# MOSFET_Sheet.net
KiCad netlist of a schematic drawn in Altium Designer
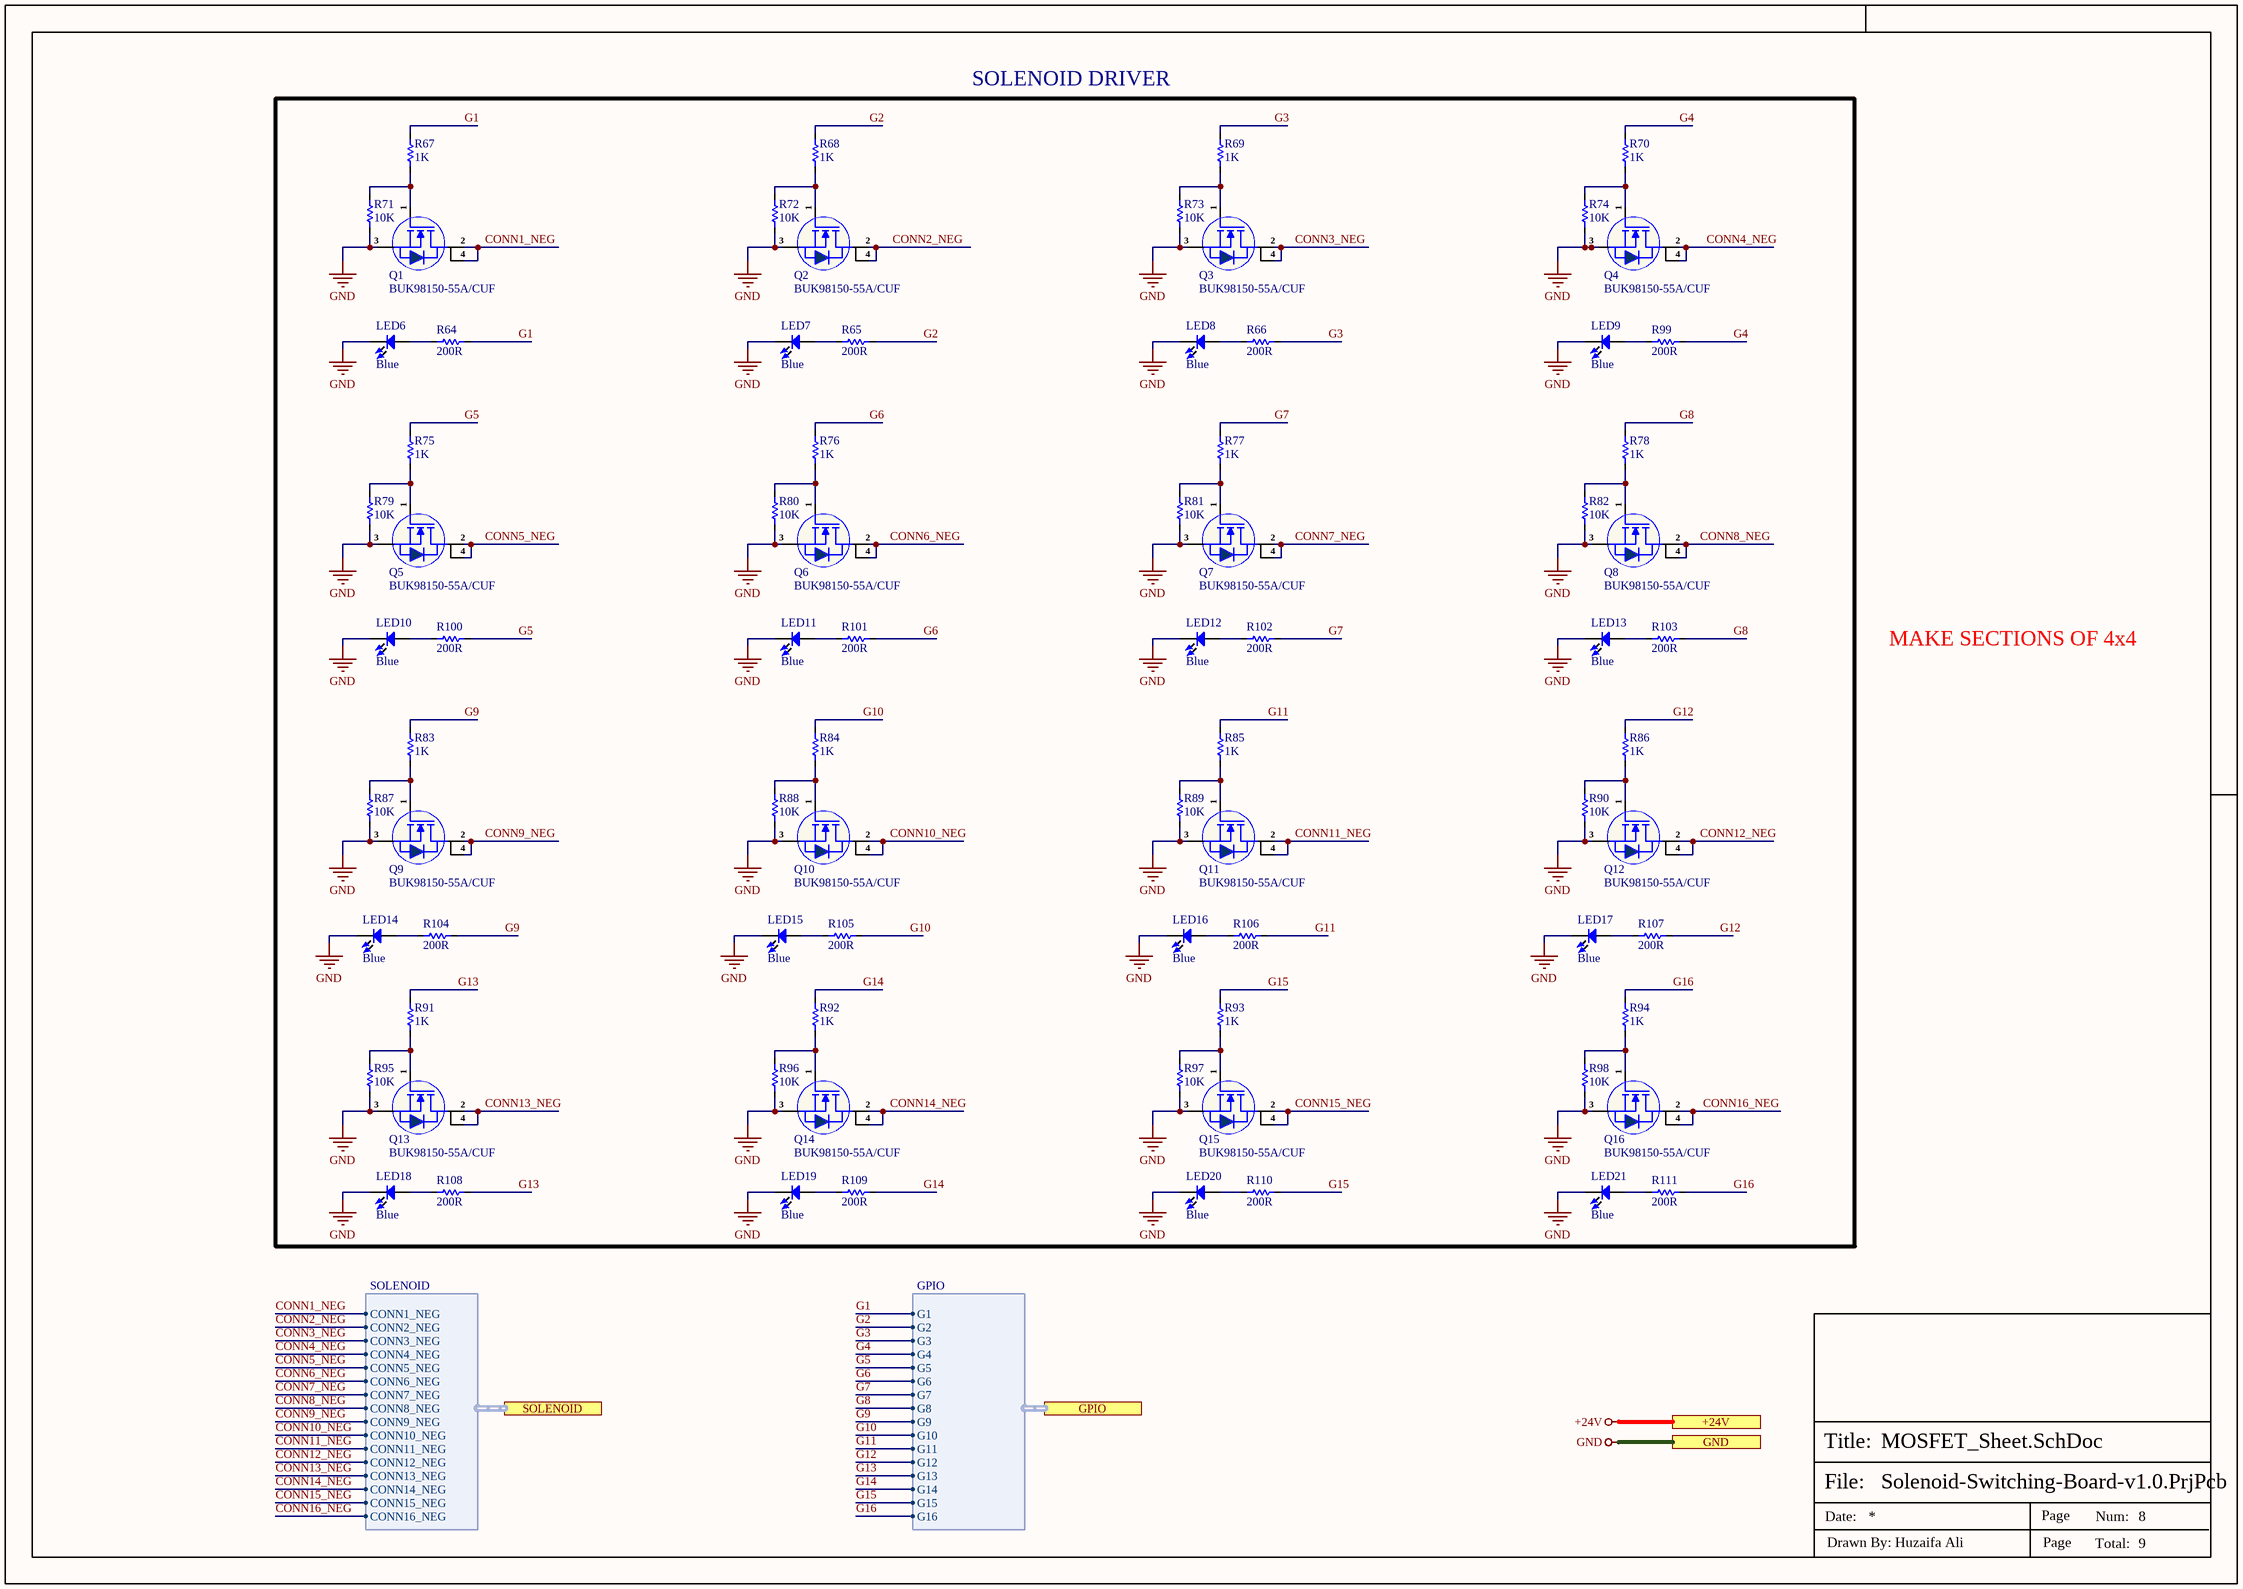
[diagram p0: MOSFET_Sheet.SchDoc]

(export (version "E")
  (design (tool "Eeschema 10.0.6"))
  (components
    (comp (ref "LED6")
      (value "Blue")
      (footprint "LED-0603")
      (description "blue 0603 Light Emitting Diodes (LED) ROHS")
      (fields
        (field (name "MANUFACTURER") "Foshan NationStar Optoelectronics")
        (field (name "MANUFACTURER PART NUMBER") "NCD0603B3")
      )
      (libsource (lib "eSpark Libraries") (part "NCD0603B3"))
    )
    (comp (ref "LED7")
      (value "Blue")
      (footprint "LED-0603")
      (description "blue 0603 Light Emitting Diodes (LED) ROHS")
      (fields
        (field (name "MANUFACTURER") "Foshan NationStar Optoelectronics")
        (field (name "MANUFACTURER PART NUMBER") "NCD0603B3")
      )
      (libsource (lib "eSpark Libraries") (part "NCD0603B3"))
    )
    (comp (ref "LED8")
      (value "Blue")
      (footprint "LED-0603")
      (description "blue 0603 Light Emitting Diodes (LED) ROHS")
      (fields
        (field (name "MANUFACTURER") "Foshan NationStar Optoelectronics")
        (field (name "MANUFACTURER PART NUMBER") "NCD0603B3")
      )
      (libsource (lib "eSpark Libraries") (part "NCD0603B3"))
    )
    (comp (ref "LED9")
      (value "Blue")
      (footprint "LED-0603")
      (description "blue 0603 Light Emitting Diodes (LED) ROHS")
      (fields
        (field (name "MANUFACTURER") "Foshan NationStar Optoelectronics")
        (field (name "MANUFACTURER PART NUMBER") "NCD0603B3")
      )
      (libsource (lib "eSpark Libraries") (part "NCD0603B3"))
    )
    (comp (ref "LED10")
      (value "Blue")
      (footprint "LED-0603")
      (description "blue 0603 Light Emitting Diodes (LED) ROHS")
      (fields
        (field (name "MANUFACTURER") "Foshan NationStar Optoelectronics")
        (field (name "MANUFACTURER PART NUMBER") "NCD0603B3")
      )
      (libsource (lib "eSpark Libraries") (part "NCD0603B3"))
    )
    (comp (ref "LED11")
      (value "Blue")
      (footprint "LED-0603")
      (description "blue 0603 Light Emitting Diodes (LED) ROHS")
      (fields
        (field (name "MANUFACTURER") "Foshan NationStar Optoelectronics")
        (field (name "MANUFACTURER PART NUMBER") "NCD0603B3")
      )
      (libsource (lib "eSpark Libraries") (part "NCD0603B3"))
    )
    (comp (ref "LED12")
      (value "Blue")
      (footprint "LED-0603")
      (description "blue 0603 Light Emitting Diodes (LED) ROHS")
      (fields
        (field (name "MANUFACTURER") "Foshan NationStar Optoelectronics")
        (field (name "MANUFACTURER PART NUMBER") "NCD0603B3")
      )
      (libsource (lib "eSpark Libraries") (part "NCD0603B3"))
    )
    (comp (ref "LED13")
      (value "Blue")
      (footprint "LED-0603")
      (description "blue 0603 Light Emitting Diodes (LED) ROHS")
      (fields
        (field (name "MANUFACTURER") "Foshan NationStar Optoelectronics")
        (field (name "MANUFACTURER PART NUMBER") "NCD0603B3")
      )
      (libsource (lib "eSpark Libraries") (part "NCD0603B3"))
    )
    (comp (ref "LED14")
      (value "Blue")
      (footprint "LED-0603")
      (description "blue 0603 Light Emitting Diodes (LED) ROHS")
      (fields
        (field (name "MANUFACTURER") "Foshan NationStar Optoelectronics")
        (field (name "MANUFACTURER PART NUMBER") "NCD0603B3")
      )
      (libsource (lib "eSpark Libraries") (part "NCD0603B3"))
    )
    (comp (ref "LED15")
      (value "Blue")
      (footprint "LED-0603")
      (description "blue 0603 Light Emitting Diodes (LED) ROHS")
      (fields
        (field (name "MANUFACTURER") "Foshan NationStar Optoelectronics")
        (field (name "MANUFACTURER PART NUMBER") "NCD0603B3")
      )
      (libsource (lib "eSpark Libraries") (part "NCD0603B3"))
    )
    (comp (ref "LED16")
      (value "Blue")
      (footprint "LED-0603")
      (description "blue 0603 Light Emitting Diodes (LED) ROHS")
      (fields
        (field (name "MANUFACTURER") "Foshan NationStar Optoelectronics")
        (field (name "MANUFACTURER PART NUMBER") "NCD0603B3")
      )
      (libsource (lib "eSpark Libraries") (part "NCD0603B3"))
    )
    (comp (ref "LED17")
      (value "Blue")
      (footprint "LED-0603")
      (description "blue 0603 Light Emitting Diodes (LED) ROHS")
      (fields
        (field (name "MANUFACTURER") "Foshan NationStar Optoelectronics")
        (field (name "MANUFACTURER PART NUMBER") "NCD0603B3")
      )
      (libsource (lib "eSpark Libraries") (part "NCD0603B3"))
    )
    (comp (ref "LED18")
      (value "Blue")
      (footprint "LED-0603")
      (description "blue 0603 Light Emitting Diodes (LED) ROHS")
      (fields
        (field (name "MANUFACTURER") "Foshan NationStar Optoelectronics")
        (field (name "MANUFACTURER PART NUMBER") "NCD0603B3")
      )
      (libsource (lib "eSpark Libraries") (part "NCD0603B3"))
    )
    (comp (ref "LED19")
      (value "Blue")
      (footprint "LED-0603")
      (description "blue 0603 Light Emitting Diodes (LED) ROHS")
      (fields
        (field (name "MANUFACTURER") "Foshan NationStar Optoelectronics")
        (field (name "MANUFACTURER PART NUMBER") "NCD0603B3")
      )
      (libsource (lib "eSpark Libraries") (part "NCD0603B3"))
    )
    (comp (ref "LED20")
      (value "Blue")
      (footprint "LED-0603")
      (description "blue 0603 Light Emitting Diodes (LED) ROHS")
      (fields
        (field (name "MANUFACTURER") "Foshan NationStar Optoelectronics")
        (field (name "MANUFACTURER PART NUMBER") "NCD0603B3")
      )
      (libsource (lib "eSpark Libraries") (part "NCD0603B3"))
    )
    (comp (ref "LED21")
      (value "Blue")
      (footprint "LED-0603")
      (description "blue 0603 Light Emitting Diodes (LED) ROHS")
      (fields
        (field (name "MANUFACTURER") "Foshan NationStar Optoelectronics")
        (field (name "MANUFACTURER PART NUMBER") "NCD0603B3")
      )
      (libsource (lib "eSpark Libraries") (part "NCD0603B3"))
    )
    (comp (ref "Q1")
      (value "BUK98150-55A/CUF")
      (footprint "SOT- 223")
      (description "MOSFET N-CH 55V 5.5A SOT223")
      (fields (field (name "LCSC PART NUMBER") "C458219") (field (name "MANUFACTURER") "Nexperia"))
      (libsource (lib "eSpark Libraries") (part "BUK98150-55A/CUF"))
    )
    (comp (ref "Q2")
      (value "BUK98150-55A/CUF")
      (footprint "SOT- 223")
      (description "MOSFET N-CH 55V 5.5A SOT223")
      (fields (field (name "LCSC PART NUMBER") "C458219") (field (name "MANUFACTURER") "Nexperia"))
      (libsource (lib "eSpark Libraries") (part "BUK98150-55A/CUF"))
    )
    (comp (ref "Q3")
      (value "BUK98150-55A/CUF")
      (footprint "SOT- 223")
      (description "MOSFET N-CH 55V 5.5A SOT223")
      (fields (field (name "LCSC PART NUMBER") "C458219") (field (name "MANUFACTURER") "Nexperia"))
      (libsource (lib "eSpark Libraries") (part "BUK98150-55A/CUF"))
    )
    (comp (ref "Q4")
      (value "BUK98150-55A/CUF")
      (footprint "SOT- 223")
      (description "MOSFET N-CH 55V 5.5A SOT223")
      (fields (field (name "LCSC PART NUMBER") "C458219") (field (name "MANUFACTURER") "Nexperia"))
      (libsource (lib "eSpark Libraries") (part "BUK98150-55A/CUF"))
    )
    (comp (ref "Q5")
      (value "BUK98150-55A/CUF")
      (footprint "SOT- 223")
      (description "MOSFET N-CH 55V 5.5A SOT223")
      (fields (field (name "LCSC PART NUMBER") "C458219") (field (name "MANUFACTURER") "Nexperia"))
      (libsource (lib "eSpark Libraries") (part "BUK98150-55A/CUF"))
    )
    (comp (ref "Q6")
      (value "BUK98150-55A/CUF")
      (footprint "SOT- 223")
      (description "MOSFET N-CH 55V 5.5A SOT223")
      (fields (field (name "LCSC PART NUMBER") "C458219") (field (name "MANUFACTURER") "Nexperia"))
      (libsource (lib "eSpark Libraries") (part "BUK98150-55A/CUF"))
    )
    (comp (ref "Q7")
      (value "BUK98150-55A/CUF")
      (footprint "SOT- 223")
      (description "MOSFET N-CH 55V 5.5A SOT223")
      (fields (field (name "LCSC PART NUMBER") "C458219") (field (name "MANUFACTURER") "Nexperia"))
      (libsource (lib "eSpark Libraries") (part "BUK98150-55A/CUF"))
    )
    (comp (ref "Q8")
      (value "BUK98150-55A/CUF")
      (footprint "SOT- 223")
      (description "MOSFET N-CH 55V 5.5A SOT223")
      (fields (field (name "LCSC PART NUMBER") "C458219") (field (name "MANUFACTURER") "Nexperia"))
      (libsource (lib "eSpark Libraries") (part "BUK98150-55A/CUF"))
    )
    (comp (ref "Q9")
      (value "BUK98150-55A/CUF")
      (footprint "SOT- 223")
      (description "MOSFET N-CH 55V 5.5A SOT223")
      (fields (field (name "LCSC PART NUMBER") "C458219") (field (name "MANUFACTURER") "Nexperia"))
      (libsource (lib "eSpark Libraries") (part "BUK98150-55A/CUF"))
    )
    (comp (ref "Q10")
      (value "BUK98150-55A/CUF")
      (footprint "SOT- 223")
      (description "MOSFET N-CH 55V 5.5A SOT223")
      (fields (field (name "LCSC PART NUMBER") "C458219") (field (name "MANUFACTURER") "Nexperia"))
      (libsource (lib "eSpark Libraries") (part "BUK98150-55A/CUF"))
    )
    (comp (ref "Q11")
      (value "BUK98150-55A/CUF")
      (footprint "SOT- 223")
      (description "MOSFET N-CH 55V 5.5A SOT223")
      (fields (field (name "LCSC PART NUMBER") "C458219") (field (name "MANUFACTURER") "Nexperia"))
      (libsource (lib "eSpark Libraries") (part "BUK98150-55A/CUF"))
    )
    (comp (ref "Q12")
      (value "BUK98150-55A/CUF")
      (footprint "SOT- 223")
      (description "MOSFET N-CH 55V 5.5A SOT223")
      (fields (field (name "LCSC PART NUMBER") "C458219") (field (name "MANUFACTURER") "Nexperia"))
      (libsource (lib "eSpark Libraries") (part "BUK98150-55A/CUF"))
    )
    (comp (ref "Q13")
      (value "BUK98150-55A/CUF")
      (footprint "SOT- 223")
      (description "MOSFET N-CH 55V 5.5A SOT223")
      (fields (field (name "LCSC PART NUMBER") "C458219") (field (name "MANUFACTURER") "Nexperia"))
      (libsource (lib "eSpark Libraries") (part "BUK98150-55A/CUF"))
    )
    (comp (ref "Q14")
      (value "BUK98150-55A/CUF")
      (footprint "SOT- 223")
      (description "MOSFET N-CH 55V 5.5A SOT223")
      (fields (field (name "LCSC PART NUMBER") "C458219") (field (name "MANUFACTURER") "Nexperia"))
      (libsource (lib "eSpark Libraries") (part "BUK98150-55A/CUF"))
    )
    (comp (ref "Q15")
      (value "BUK98150-55A/CUF")
      (footprint "SOT- 223")
      (description "MOSFET N-CH 55V 5.5A SOT223")
      (fields (field (name "LCSC PART NUMBER") "C458219") (field (name "MANUFACTURER") "Nexperia"))
      (libsource (lib "eSpark Libraries") (part "BUK98150-55A/CUF"))
    )
    (comp (ref "Q16")
      (value "BUK98150-55A/CUF")
      (footprint "SOT- 223")
      (description "MOSFET N-CH 55V 5.5A SOT223")
      (fields (field (name "LCSC PART NUMBER") "C458219") (field (name "MANUFACTURER") "Nexperia"))
      (libsource (lib "eSpark Libraries") (part "BUK98150-55A/CUF"))
    )
    (comp (ref "R64")
      (value "200R")
      (footprint "Res-0402")
      (description "RES 200 OHM 1% 1/16W 0402")
      (fields
        (field (name "MANUFACTURER") "Yageo")
        (field (name "MANUFACTURER PART NUMBER") "RC0402FR-07200RL")
      )
      (libsource (lib "eSpark Libraries") (part "RC0402FR-07200RL"))
    )
    (comp (ref "R65")
      (value "200R")
      (footprint "Res-0402")
      (description "RES 200 OHM 1% 1/16W 0402")
      (fields
        (field (name "MANUFACTURER") "Yageo")
        (field (name "MANUFACTURER PART NUMBER") "RC0402FR-07200RL")
      )
      (libsource (lib "eSpark Libraries") (part "RC0402FR-07200RL"))
    )
    (comp (ref "R66")
      (value "200R")
      (footprint "Res-0402")
      (description "RES 200 OHM 1% 1/16W 0402")
      (fields
        (field (name "MANUFACTURER") "Yageo")
        (field (name "MANUFACTURER PART NUMBER") "RC0402FR-07200RL")
      )
      (libsource (lib "eSpark Libraries") (part "RC0402FR-07200RL"))
    )
    (comp (ref "R67")
      (value "1K")
      (footprint "Res-0402")
      (description "RES 1K OHM 1% 1/16W 0402")
      (fields
        (field (name "MANUFACTURER") "Yageo")
        (field (name "MANUFACTURER PART NUMBER") "RC0402FR-071KL")
      )
      (libsource (lib "eSpark Libraries") (part "RC0402FR-071KL"))
    )
    (comp (ref "R68")
      (value "1K")
      (footprint "Res-0402")
      (description "RES 1K OHM 1% 1/16W 0402")
      (fields
        (field (name "MANUFACTURER") "Yageo")
        (field (name "MANUFACTURER PART NUMBER") "RC0402FR-071KL")
      )
      (libsource (lib "eSpark Libraries") (part "RC0402FR-071KL"))
    )
    (comp (ref "R69")
      (value "1K")
      (footprint "Res-0402")
      (description "RES 1K OHM 1% 1/16W 0402")
      (fields
        (field (name "MANUFACTURER") "Yageo")
        (field (name "MANUFACTURER PART NUMBER") "RC0402FR-071KL")
      )
      (libsource (lib "eSpark Libraries") (part "RC0402FR-071KL"))
    )
    (comp (ref "R70")
      (value "1K")
      (footprint "Res-0402")
      (description "RES 1K OHM 1% 1/16W 0402")
      (fields
        (field (name "MANUFACTURER") "Yageo")
        (field (name "MANUFACTURER PART NUMBER") "RC0402FR-071KL")
      )
      (libsource (lib "eSpark Libraries") (part "RC0402FR-071KL"))
    )
    (comp (ref "R71")
      (value "10K")
      (footprint "Res-0402")
      (description "RES 10K OHM 1% 1/16W 0402")
      (fields
        (field (name "MANUFACTURER") "Yageo")
        (field (name "MANUFACTURER PART NUMBER") "RC0402FR-0710KL")
      )
      (libsource (lib "eSpark Libraries") (part "RC0402FR-0710KL"))
    )
    (comp (ref "R72")
      (value "10K")
      (footprint "Res-0402")
      (description "RES 10K OHM 1% 1/16W 0402")
      (fields
        (field (name "MANUFACTURER") "Yageo")
        (field (name "MANUFACTURER PART NUMBER") "RC0402FR-0710KL")
      )
      (libsource (lib "eSpark Libraries") (part "RC0402FR-0710KL"))
    )
    (comp (ref "R73")
      (value "10K")
      (footprint "Res-0402")
      (description "RES 10K OHM 1% 1/16W 0402")
      (fields
        (field (name "MANUFACTURER") "Yageo")
        (field (name "MANUFACTURER PART NUMBER") "RC0402FR-0710KL")
      )
      (libsource (lib "eSpark Libraries") (part "RC0402FR-0710KL"))
    )
    (comp (ref "R74")
      (value "10K")
      (footprint "Res-0402")
      (description "RES 10K OHM 1% 1/16W 0402")
      (fields
        (field (name "MANUFACTURER") "Yageo")
        (field (name "MANUFACTURER PART NUMBER") "RC0402FR-0710KL")
      )
      (libsource (lib "eSpark Libraries") (part "RC0402FR-0710KL"))
    )
    (comp (ref "R75")
      (value "1K")
      (footprint "Res-0402")
      (description "RES 1K OHM 1% 1/16W 0402")
      (fields
        (field (name "MANUFACTURER") "Yageo")
        (field (name "MANUFACTURER PART NUMBER") "RC0402FR-071KL")
      )
      (libsource (lib "eSpark Libraries") (part "RC0402FR-071KL"))
    )
    (comp (ref "R76")
      (value "1K")
      (footprint "Res-0402")
      (description "RES 1K OHM 1% 1/16W 0402")
      (fields
        (field (name "MANUFACTURER") "Yageo")
        (field (name "MANUFACTURER PART NUMBER") "RC0402FR-071KL")
      )
      (libsource (lib "eSpark Libraries") (part "RC0402FR-071KL"))
    )
    (comp (ref "R77")
      (value "1K")
      (footprint "Res-0402")
      (description "RES 1K OHM 1% 1/16W 0402")
      (fields
        (field (name "MANUFACTURER") "Yageo")
        (field (name "MANUFACTURER PART NUMBER") "RC0402FR-071KL")
      )
      (libsource (lib "eSpark Libraries") (part "RC0402FR-071KL"))
    )
    (comp (ref "R78")
      (value "1K")
      (footprint "Res-0402")
      (description "RES 1K OHM 1% 1/16W 0402")
      (fields
        (field (name "MANUFACTURER") "Yageo")
        (field (name "MANUFACTURER PART NUMBER") "RC0402FR-071KL")
      )
      (libsource (lib "eSpark Libraries") (part "RC0402FR-071KL"))
    )
    (comp (ref "R79")
      (value "10K")
      (footprint "Res-0402")
      (description "RES 10K OHM 1% 1/16W 0402")
      (fields
        (field (name "MANUFACTURER") "Yageo")
        (field (name "MANUFACTURER PART NUMBER") "RC0402FR-0710KL")
      )
      (libsource (lib "eSpark Libraries") (part "RC0402FR-0710KL"))
    )
    (comp (ref "R80")
      (value "10K")
      (footprint "Res-0402")
      (description "RES 10K OHM 1% 1/16W 0402")
      (fields
        (field (name "MANUFACTURER") "Yageo")
        (field (name "MANUFACTURER PART NUMBER") "RC0402FR-0710KL")
      )
      (libsource (lib "eSpark Libraries") (part "RC0402FR-0710KL"))
    )
    (comp (ref "R81")
      (value "10K")
      (footprint "Res-0402")
      (description "RES 10K OHM 1% 1/16W 0402")
      (fields
        (field (name "MANUFACTURER") "Yageo")
        (field (name "MANUFACTURER PART NUMBER") "RC0402FR-0710KL")
      )
      (libsource (lib "eSpark Libraries") (part "RC0402FR-0710KL"))
    )
    (comp (ref "R82")
      (value "10K")
      (footprint "Res-0402")
      (description "RES 10K OHM 1% 1/16W 0402")
      (fields
        (field (name "MANUFACTURER") "Yageo")
        (field (name "MANUFACTURER PART NUMBER") "RC0402FR-0710KL")
      )
      (libsource (lib "eSpark Libraries") (part "RC0402FR-0710KL"))
    )
    (comp (ref "R83")
      (value "1K")
      (footprint "Res-0402")
      (description "RES 1K OHM 1% 1/16W 0402")
      (fields
        (field (name "MANUFACTURER") "Yageo")
        (field (name "MANUFACTURER PART NUMBER") "RC0402FR-071KL")
      )
      (libsource (lib "eSpark Libraries") (part "RC0402FR-071KL"))
    )
    (comp (ref "R84")
      (value "1K")
      (footprint "Res-0402")
      (description "RES 1K OHM 1% 1/16W 0402")
      (fields
        (field (name "MANUFACTURER") "Yageo")
        (field (name "MANUFACTURER PART NUMBER") "RC0402FR-071KL")
      )
      (libsource (lib "eSpark Libraries") (part "RC0402FR-071KL"))
    )
    (comp (ref "R85")
      (value "1K")
      (footprint "Res-0402")
      (description "RES 1K OHM 1% 1/16W 0402")
      (fields
        (field (name "MANUFACTURER") "Yageo")
        (field (name "MANUFACTURER PART NUMBER") "RC0402FR-071KL")
      )
      (libsource (lib "eSpark Libraries") (part "RC0402FR-071KL"))
    )
    (comp (ref "R86")
      (value "1K")
      (footprint "Res-0402")
      (description "RES 1K OHM 1% 1/16W 0402")
      (fields
        (field (name "MANUFACTURER") "Yageo")
        (field (name "MANUFACTURER PART NUMBER") "RC0402FR-071KL")
      )
      (libsource (lib "eSpark Libraries") (part "RC0402FR-071KL"))
    )
    (comp (ref "R87")
      (value "10K")
      (footprint "Res-0402")
      (description "RES 10K OHM 1% 1/16W 0402")
      (fields
        (field (name "MANUFACTURER") "Yageo")
        (field (name "MANUFACTURER PART NUMBER") "RC0402FR-0710KL")
      )
      (libsource (lib "eSpark Libraries") (part "RC0402FR-0710KL"))
    )
    (comp (ref "R88")
      (value "10K")
      (footprint "Res-0402")
      (description "RES 10K OHM 1% 1/16W 0402")
      (fields
        (field (name "MANUFACTURER") "Yageo")
        (field (name "MANUFACTURER PART NUMBER") "RC0402FR-0710KL")
      )
      (libsource (lib "eSpark Libraries") (part "RC0402FR-0710KL"))
    )
    (comp (ref "R89")
      (value "10K")
      (footprint "Res-0402")
      (description "RES 10K OHM 1% 1/16W 0402")
      (fields
        (field (name "MANUFACTURER") "Yageo")
        (field (name "MANUFACTURER PART NUMBER") "RC0402FR-0710KL")
      )
      (libsource (lib "eSpark Libraries") (part "RC0402FR-0710KL"))
    )
    (comp (ref "R90")
      (value "10K")
      (footprint "Res-0402")
      (description "RES 10K OHM 1% 1/16W 0402")
      (fields
        (field (name "MANUFACTURER") "Yageo")
        (field (name "MANUFACTURER PART NUMBER") "RC0402FR-0710KL")
      )
      (libsource (lib "eSpark Libraries") (part "RC0402FR-0710KL"))
    )
    (comp (ref "R91")
      (value "1K")
      (footprint "Res-0402")
      (description "RES 1K OHM 1% 1/16W 0402")
      (fields
        (field (name "MANUFACTURER") "Yageo")
        (field (name "MANUFACTURER PART NUMBER") "RC0402FR-071KL")
      )
      (libsource (lib "eSpark Libraries") (part "RC0402FR-071KL"))
    )
    (comp (ref "R92")
      (value "1K")
      (footprint "Res-0402")
      (description "RES 1K OHM 1% 1/16W 0402")
      (fields
        (field (name "MANUFACTURER") "Yageo")
        (field (name "MANUFACTURER PART NUMBER") "RC0402FR-071KL")
      )
      (libsource (lib "eSpark Libraries") (part "RC0402FR-071KL"))
    )
    (comp (ref "R93")
      (value "1K")
      (footprint "Res-0402")
      (description "RES 1K OHM 1% 1/16W 0402")
      (fields
        (field (name "MANUFACTURER") "Yageo")
        (field (name "MANUFACTURER PART NUMBER") "RC0402FR-071KL")
      )
      (libsource (lib "eSpark Libraries") (part "RC0402FR-071KL"))
    )
    (comp (ref "R94")
      (value "1K")
      (footprint "Res-0402")
      (description "RES 1K OHM 1% 1/16W 0402")
      (fields
        (field (name "MANUFACTURER") "Yageo")
        (field (name "MANUFACTURER PART NUMBER") "RC0402FR-071KL")
      )
      (libsource (lib "eSpark Libraries") (part "RC0402FR-071KL"))
    )
    (comp (ref "R95")
      (value "10K")
      (footprint "Res-0402")
      (description "RES 10K OHM 1% 1/16W 0402")
      (fields
        (field (name "MANUFACTURER") "Yageo")
        (field (name "MANUFACTURER PART NUMBER") "RC0402FR-0710KL")
      )
      (libsource (lib "eSpark Libraries") (part "RC0402FR-0710KL"))
    )
    (comp (ref "R96")
      (value "10K")
      (footprint "Res-0402")
      (description "RES 10K OHM 1% 1/16W 0402")
      (fields
        (field (name "MANUFACTURER") "Yageo")
        (field (name "MANUFACTURER PART NUMBER") "RC0402FR-0710KL")
      )
      (libsource (lib "eSpark Libraries") (part "RC0402FR-0710KL"))
    )
    (comp (ref "R97")
      (value "10K")
      (footprint "Res-0402")
      (description "RES 10K OHM 1% 1/16W 0402")
      (fields
        (field (name "MANUFACTURER") "Yageo")
        (field (name "MANUFACTURER PART NUMBER") "RC0402FR-0710KL")
      )
      (libsource (lib "eSpark Libraries") (part "RC0402FR-0710KL"))
    )
    (comp (ref "R98")
      (value "10K")
      (footprint "Res-0402")
      (description "RES 10K OHM 1% 1/16W 0402")
      (fields
        (field (name "MANUFACTURER") "Yageo")
        (field (name "MANUFACTURER PART NUMBER") "RC0402FR-0710KL")
      )
      (libsource (lib "eSpark Libraries") (part "RC0402FR-0710KL"))
    )
    (comp (ref "R99")
      (value "200R")
      (footprint "Res-0402")
      (description "RES 200 OHM 1% 1/16W 0402")
      (fields
        (field (name "MANUFACTURER") "Yageo")
        (field (name "MANUFACTURER PART NUMBER") "RC0402FR-07200RL")
      )
      (libsource (lib "eSpark Libraries") (part "RC0402FR-07200RL"))
    )
    (comp (ref "R100")
      (value "200R")
      (footprint "Res-0402")
      (description "RES 200 OHM 1% 1/16W 0402")
      (fields
        (field (name "MANUFACTURER") "Yageo")
        (field (name "MANUFACTURER PART NUMBER") "RC0402FR-07200RL")
      )
      (libsource (lib "eSpark Libraries") (part "RC0402FR-07200RL"))
    )
    (comp (ref "R101")
      (value "200R")
      (footprint "Res-0402")
      (description "RES 200 OHM 1% 1/16W 0402")
      (fields
        (field (name "MANUFACTURER") "Yageo")
        (field (name "MANUFACTURER PART NUMBER") "RC0402FR-07200RL")
      )
      (libsource (lib "eSpark Libraries") (part "RC0402FR-07200RL"))
    )
    (comp (ref "R102")
      (value "200R")
      (footprint "Res-0402")
      (description "RES 200 OHM 1% 1/16W 0402")
      (fields
        (field (name "MANUFACTURER") "Yageo")
        (field (name "MANUFACTURER PART NUMBER") "RC0402FR-07200RL")
      )
      (libsource (lib "eSpark Libraries") (part "RC0402FR-07200RL"))
    )
    (comp (ref "R103")
      (value "200R")
      (footprint "Res-0402")
      (description "RES 200 OHM 1% 1/16W 0402")
      (fields
        (field (name "MANUFACTURER") "Yageo")
        (field (name "MANUFACTURER PART NUMBER") "RC0402FR-07200RL")
      )
      (libsource (lib "eSpark Libraries") (part "RC0402FR-07200RL"))
    )
    (comp (ref "R104")
      (value "200R")
      (footprint "Res-0402")
      (description "RES 200 OHM 1% 1/16W 0402")
      (fields
        (field (name "MANUFACTURER") "Yageo")
        (field (name "MANUFACTURER PART NUMBER") "RC0402FR-07200RL")
      )
      (libsource (lib "eSpark Libraries") (part "RC0402FR-07200RL"))
    )
    (comp (ref "R105")
      (value "200R")
      (footprint "Res-0402")
      (description "RES 200 OHM 1% 1/16W 0402")
      (fields
        (field (name "MANUFACTURER") "Yageo")
        (field (name "MANUFACTURER PART NUMBER") "RC0402FR-07200RL")
      )
      (libsource (lib "eSpark Libraries") (part "RC0402FR-07200RL"))
    )
    (comp (ref "R106")
      (value "200R")
      (footprint "Res-0402")
      (description "RES 200 OHM 1% 1/16W 0402")
      (fields
        (field (name "MANUFACTURER") "Yageo")
        (field (name "MANUFACTURER PART NUMBER") "RC0402FR-07200RL")
      )
      (libsource (lib "eSpark Libraries") (part "RC0402FR-07200RL"))
    )
    (comp (ref "R107")
      (value "200R")
      (footprint "Res-0402")
      (description "RES 200 OHM 1% 1/16W 0402")
      (fields
        (field (name "MANUFACTURER") "Yageo")
        (field (name "MANUFACTURER PART NUMBER") "RC0402FR-07200RL")
      )
      (libsource (lib "eSpark Libraries") (part "RC0402FR-07200RL"))
    )
    (comp (ref "R108")
      (value "200R")
      (footprint "Res-0402")
      (description "RES 200 OHM 1% 1/16W 0402")
      (fields
        (field (name "MANUFACTURER") "Yageo")
        (field (name "MANUFACTURER PART NUMBER") "RC0402FR-07200RL")
      )
      (libsource (lib "eSpark Libraries") (part "RC0402FR-07200RL"))
    )
    (comp (ref "R109")
      (value "200R")
      (footprint "Res-0402")
      (description "RES 200 OHM 1% 1/16W 0402")
      (fields
        (field (name "MANUFACTURER") "Yageo")
        (field (name "MANUFACTURER PART NUMBER") "RC0402FR-07200RL")
      )
      (libsource (lib "eSpark Libraries") (part "RC0402FR-07200RL"))
    )
    (comp (ref "R110")
      (value "200R")
      (footprint "Res-0402")
      (description "RES 200 OHM 1% 1/16W 0402")
      (fields
        (field (name "MANUFACTURER") "Yageo")
        (field (name "MANUFACTURER PART NUMBER") "RC0402FR-07200RL")
      )
      (libsource (lib "eSpark Libraries") (part "RC0402FR-07200RL"))
    )
    (comp (ref "R111")
      (value "200R")
      (footprint "Res-0402")
      (description "RES 200 OHM 1% 1/16W 0402")
      (fields
        (field (name "MANUFACTURER") "Yageo")
        (field (name "MANUFACTURER PART NUMBER") "RC0402FR-07200RL")
      )
      (libsource (lib "eSpark Libraries") (part "RC0402FR-07200RL"))
    )
  )
  (nets
    (net (code "4") (name "/CONN1_NEG") (class "Default")
      (node (ref "Q1") (pin "2") (pinfunction "D_2") (pintype "passive"))
      (node (ref "Q1") (pin "4") (pinfunction "D_4") (pintype "passive"))
    )
    (net (code "5") (name "/CONN2_NEG") (class "Default")
      (node (ref "Q2") (pin "2") (pinfunction "D_2") (pintype "passive"))
      (node (ref "Q2") (pin "4") (pinfunction "D_4") (pintype "passive"))
    )
    (net (code "6") (name "/CONN3_NEG") (class "Default")
      (node (ref "Q3") (pin "2") (pinfunction "D_2") (pintype "passive"))
      (node (ref "Q3") (pin "4") (pinfunction "D_4") (pintype "passive"))
    )
    (net (code "7") (name "/CONN4_NEG") (class "Default")
      (node (ref "Q4") (pin "2") (pinfunction "D_2") (pintype "passive"))
      (node (ref "Q4") (pin "4") (pinfunction "D_4") (pintype "passive"))
    )
    (net (code "8") (name "/CONN5_NEG") (class "Default")
      (node (ref "Q5") (pin "2") (pinfunction "D_2") (pintype "passive"))
      (node (ref "Q5") (pin "4") (pinfunction "D_4") (pintype "passive"))
    )
    (net (code "9") (name "/CONN6_NEG") (class "Default")
      (node (ref "Q6") (pin "2") (pinfunction "D_2") (pintype "passive"))
      (node (ref "Q6") (pin "4") (pinfunction "D_4") (pintype "passive"))
    )
    (net (code "10") (name "/CONN7_NEG") (class "Default")
      (node (ref "Q7") (pin "2") (pinfunction "D_2") (pintype "passive"))
      (node (ref "Q7") (pin "4") (pinfunction "D_4") (pintype "passive"))
    )
    (net (code "11") (name "/CONN8_NEG") (class "Default")
      (node (ref "Q8") (pin "2") (pinfunction "D_2") (pintype "passive"))
      (node (ref "Q8") (pin "4") (pinfunction "D_4") (pintype "passive"))
    )
    (net (code "12") (name "/CONN9_NEG") (class "Default")
      (node (ref "Q9") (pin "2") (pinfunction "D_2") (pintype "passive"))
      (node (ref "Q9") (pin "4") (pinfunction "D_4") (pintype "passive"))
    )
    (net (code "13") (name "/CONN10_NEG") (class "Default")
      (node (ref "Q10") (pin "2") (pinfunction "D_2") (pintype "passive"))
      (node (ref "Q10") (pin "4") (pinfunction "D_4") (pintype "passive"))
    )
    (net (code "14") (name "/CONN11_NEG") (class "Default")
      (node (ref "Q11") (pin "2") (pinfunction "D_2") (pintype "passive"))
      (node (ref "Q11") (pin "4") (pinfunction "D_4") (pintype "passive"))
    )
    (net (code "15") (name "/CONN12_NEG") (class "Default")
      (node (ref "Q12") (pin "2") (pinfunction "D_2") (pintype "passive"))
      (node (ref "Q12") (pin "4") (pinfunction "D_4") (pintype "passive"))
    )
    (net (code "16") (name "/CONN13_NEG") (class "Default")
      (node (ref "Q13") (pin "2") (pinfunction "D_2") (pintype "passive"))
      (node (ref "Q13") (pin "4") (pinfunction "D_4") (pintype "passive"))
    )
    (net (code "17") (name "/CONN14_NEG") (class "Default")
      (node (ref "Q14") (pin "2") (pinfunction "D_2") (pintype "passive"))
      (node (ref "Q14") (pin "4") (pinfunction "D_4") (pintype "passive"))
    )
    (net (code "18") (name "/CONN15_NEG") (class "Default")
      (node (ref "Q15") (pin "2") (pinfunction "D_2") (pintype "passive"))
      (node (ref "Q15") (pin "4") (pinfunction "D_4") (pintype "passive"))
    )
    (net (code "19") (name "/CONN16_NEG") (class "Default")
      (node (ref "Q16") (pin "2") (pinfunction "D_2") (pintype "passive"))
      (node (ref "Q16") (pin "4") (pinfunction "D_4") (pintype "passive"))
    )
    (net (code "20") (name "/G1") (class "Default")
      (node (ref "R64") (pin "2") (pinfunction "2_2") (pintype "passive"))
      (node (ref "R67") (pin "2") (pinfunction "2_2") (pintype "passive"))
    )
    (net (code "21") (name "/G2") (class "Default")
      (node (ref "R65") (pin "2") (pinfunction "2_2") (pintype "passive"))
      (node (ref "R68") (pin "2") (pinfunction "2_2") (pintype "passive"))
    )
    (net (code "22") (name "/G3") (class "Default")
      (node (ref "R66") (pin "2") (pinfunction "2_2") (pintype "passive"))
      (node (ref "R69") (pin "2") (pinfunction "2_2") (pintype "passive"))
    )
    (net (code "23") (name "/G4") (class "Default")
      (node (ref "R70") (pin "2") (pinfunction "2_2") (pintype "passive"))
      (node (ref "R99") (pin "2") (pinfunction "2_2") (pintype "passive"))
    )
    (net (code "24") (name "/G5") (class "Default")
      (node (ref "R100") (pin "2") (pinfunction "2_2") (pintype "passive"))
      (node (ref "R75") (pin "2") (pinfunction "2_2") (pintype "passive"))
    )
    (net (code "25") (name "/G6") (class "Default")
      (node (ref "R101") (pin "2") (pinfunction "2_2") (pintype "passive"))
      (node (ref "R76") (pin "2") (pinfunction "2_2") (pintype "passive"))
    )
    (net (code "26") (name "/G7") (class "Default")
      (node (ref "R102") (pin "2") (pinfunction "2_2") (pintype "passive"))
      (node (ref "R77") (pin "2") (pinfunction "2_2") (pintype "passive"))
    )
    (net (code "27") (name "/G8") (class "Default")
      (node (ref "R103") (pin "2") (pinfunction "2_2") (pintype "passive"))
      (node (ref "R78") (pin "2") (pinfunction "2_2") (pintype "passive"))
    )
    (net (code "28") (name "/G9") (class "Default")
      (node (ref "R104") (pin "2") (pinfunction "2_2") (pintype "passive"))
      (node (ref "R83") (pin "2") (pinfunction "2_2") (pintype "passive"))
    )
    (net (code "29") (name "/G10") (class "Default")
      (node (ref "R105") (pin "2") (pinfunction "2_2") (pintype "passive"))
      (node (ref "R84") (pin "2") (pinfunction "2_2") (pintype "passive"))
    )
    (net (code "30") (name "/G11") (class "Default")
      (node (ref "R106") (pin "2") (pinfunction "2_2") (pintype "passive"))
      (node (ref "R85") (pin "2") (pinfunction "2_2") (pintype "passive"))
    )
    (net (code "31") (name "/G12") (class "Default")
      (node (ref "R107") (pin "2") (pinfunction "2_2") (pintype "passive"))
      (node (ref "R86") (pin "2") (pinfunction "2_2") (pintype "passive"))
    )
    (net (code "32") (name "/G13") (class "Default")
      (node (ref "R108") (pin "2") (pinfunction "2_2") (pintype "passive"))
      (node (ref "R91") (pin "2") (pinfunction "2_2") (pintype "passive"))
    )
    (net (code "33") (name "/G14") (class "Default")
      (node (ref "R109") (pin "2") (pinfunction "2_2") (pintype "passive"))
      (node (ref "R92") (pin "2") (pinfunction "2_2") (pintype "passive"))
    )
    (net (code "34") (name "/G15") (class "Default")
      (node (ref "R110") (pin "2") (pinfunction "2_2") (pintype "passive"))
      (node (ref "R93") (pin "2") (pinfunction "2_2") (pintype "passive"))
    )
    (net (code "35") (name "/G16") (class "Default")
      (node (ref "R111") (pin "2") (pinfunction "2_2") (pintype "passive"))
      (node (ref "R94") (pin "2") (pinfunction "2_2") (pintype "passive"))
    )
    (net (code "38") (name "GND") (class "Default")
      (node (ref "LED10") (pin "2") (pinfunction "2_2") (pintype "passive"))
      (node (ref "LED11") (pin "2") (pinfunction "2_2") (pintype "passive"))
      (node (ref "LED12") (pin "2") (pinfunction "2_2") (pintype "passive"))
      (node (ref "LED13") (pin "2") (pinfunction "2_2") (pintype "passive"))
      (node (ref "LED14") (pin "2") (pinfunction "2_2") (pintype "passive"))
      (node (ref "LED15") (pin "2") (pinfunction "2_2") (pintype "passive"))
      (node (ref "LED16") (pin "2") (pinfunction "2_2") (pintype "passive"))
      (node (ref "LED17") (pin "2") (pinfunction "2_2") (pintype "passive"))
      (node (ref "LED18") (pin "2") (pinfunction "2_2") (pintype "passive"))
      (node (ref "LED19") (pin "2") (pinfunction "2_2") (pintype "passive"))
      (node (ref "LED20") (pin "2") (pinfunction "2_2") (pintype "passive"))
      (node (ref "LED21") (pin "2") (pinfunction "2_2") (pintype "passive"))
      (node (ref "LED6") (pin "2") (pinfunction "2_2") (pintype "passive"))
      (node (ref "LED7") (pin "2") (pinfunction "2_2") (pintype "passive"))
      (node (ref "LED8") (pin "2") (pinfunction "2_2") (pintype "passive"))
      (node (ref "LED9") (pin "2") (pinfunction "2_2") (pintype "passive"))
      (node (ref "Q1") (pin "3") (pinfunction "S_3") (pintype "passive"))
      (node (ref "Q10") (pin "3") (pinfunction "S_3") (pintype "passive"))
      (node (ref "Q11") (pin "3") (pinfunction "S_3") (pintype "passive"))
      (node (ref "Q12") (pin "3") (pinfunction "S_3") (pintype "passive"))
      (node (ref "Q13") (pin "3") (pinfunction "S_3") (pintype "passive"))
      (node (ref "Q14") (pin "3") (pinfunction "S_3") (pintype "passive"))
      (node (ref "Q15") (pin "3") (pinfunction "S_3") (pintype "passive"))
      (node (ref "Q16") (pin "3") (pinfunction "S_3") (pintype "passive"))
      (node (ref "Q2") (pin "3") (pinfunction "S_3") (pintype "passive"))
      (node (ref "Q3") (pin "3") (pinfunction "S_3") (pintype "passive"))
      (node (ref "Q4") (pin "3") (pinfunction "S_3") (pintype "passive"))
      (node (ref "Q5") (pin "3") (pinfunction "S_3") (pintype "passive"))
      (node (ref "Q6") (pin "3") (pinfunction "S_3") (pintype "passive"))
      (node (ref "Q7") (pin "3") (pinfunction "S_3") (pintype "passive"))
      (node (ref "Q8") (pin "3") (pinfunction "S_3") (pintype "passive"))
      (node (ref "Q9") (pin "3") (pinfunction "S_3") (pintype "passive"))
      (node (ref "R71") (pin "2") (pinfunction "2_2") (pintype "passive"))
      (node (ref "R72") (pin "2") (pinfunction "2_2") (pintype "passive"))
      (node (ref "R73") (pin "2") (pinfunction "2_2") (pintype "passive"))
      (node (ref "R74") (pin "2") (pinfunction "2_2") (pintype "passive"))
      (node (ref "R79") (pin "2") (pinfunction "2_2") (pintype "passive"))
      (node (ref "R80") (pin "2") (pinfunction "2_2") (pintype "passive"))
      (node (ref "R81") (pin "2") (pinfunction "2_2") (pintype "passive"))
      (node (ref "R82") (pin "2") (pinfunction "2_2") (pintype "passive"))
      (node (ref "R87") (pin "2") (pinfunction "2_2") (pintype "passive"))
      (node (ref "R88") (pin "2") (pinfunction "2_2") (pintype "passive"))
      (node (ref "R89") (pin "2") (pinfunction "2_2") (pintype "passive"))
      (node (ref "R90") (pin "2") (pinfunction "2_2") (pintype "passive"))
      (node (ref "R95") (pin "2") (pinfunction "2_2") (pintype "passive"))
      (node (ref "R96") (pin "2") (pinfunction "2_2") (pintype "passive"))
      (node (ref "R97") (pin "2") (pinfunction "2_2") (pintype "passive"))
      (node (ref "R98") (pin "2") (pinfunction "2_2") (pintype "passive"))
    )
    (net (code "39") (name "Net-(LED6-Pad1)") (class "Default")
      (node (ref "LED6") (pin "1") (pinfunction "1_1") (pintype "passive"))
      (node (ref "R64") (pin "1") (pinfunction "1_1") (pintype "passive"))
    )
    (net (code "40") (name "Net-(LED7-Pad1)") (class "Default")
      (node (ref "LED7") (pin "1") (pinfunction "1_1") (pintype "passive"))
      (node (ref "R65") (pin "1") (pinfunction "1_1") (pintype "passive"))
    )
    (net (code "41") (name "Net-(LED8-Pad1)") (class "Default")
      (node (ref "LED8") (pin "1") (pinfunction "1_1") (pintype "passive"))
      (node (ref "R66") (pin "1") (pinfunction "1_1") (pintype "passive"))
    )
    (net (code "42") (name "Net-(LED9-Pad1)") (class "Default")
      (node (ref "LED9") (pin "1") (pinfunction "1_1") (pintype "passive"))
      (node (ref "R99") (pin "1") (pinfunction "1_1") (pintype "passive"))
    )
    (net (code "43") (name "Net-(LED10-Pad1)") (class "Default")
      (node (ref "LED10") (pin "1") (pinfunction "1_1") (pintype "passive"))
      (node (ref "R100") (pin "1") (pinfunction "1_1") (pintype "passive"))
    )
    (net (code "44") (name "Net-(LED11-Pad1)") (class "Default")
      (node (ref "LED11") (pin "1") (pinfunction "1_1") (pintype "passive"))
      (node (ref "R101") (pin "1") (pinfunction "1_1") (pintype "passive"))
    )
    (net (code "45") (name "Net-(LED12-Pad1)") (class "Default")
      (node (ref "LED12") (pin "1") (pinfunction "1_1") (pintype "passive"))
      (node (ref "R102") (pin "1") (pinfunction "1_1") (pintype "passive"))
    )
    (net (code "46") (name "Net-(LED13-Pad1)") (class "Default")
      (node (ref "LED13") (pin "1") (pinfunction "1_1") (pintype "passive"))
      (node (ref "R103") (pin "1") (pinfunction "1_1") (pintype "passive"))
    )
    (net (code "47") (name "Net-(LED14-Pad1)") (class "Default")
      (node (ref "LED14") (pin "1") (pinfunction "1_1") (pintype "passive"))
      (node (ref "R104") (pin "1") (pinfunction "1_1") (pintype "passive"))
    )
    (net (code "48") (name "Net-(LED15-Pad1)") (class "Default")
      (node (ref "LED15") (pin "1") (pinfunction "1_1") (pintype "passive"))
      (node (ref "R105") (pin "1") (pinfunction "1_1") (pintype "passive"))
    )
    (net (code "49") (name "Net-(LED16-Pad1)") (class "Default")
      (node (ref "LED16") (pin "1") (pinfunction "1_1") (pintype "passive"))
      (node (ref "R106") (pin "1") (pinfunction "1_1") (pintype "passive"))
    )
    (net (code "50") (name "Net-(LED17-Pad1)") (class "Default")
      (node (ref "LED17") (pin "1") (pinfunction "1_1") (pintype "passive"))
      (node (ref "R107") (pin "1") (pinfunction "1_1") (pintype "passive"))
    )
    (net (code "51") (name "Net-(LED18-Pad1)") (class "Default")
      (node (ref "LED18") (pin "1") (pinfunction "1_1") (pintype "passive"))
      (node (ref "R108") (pin "1") (pinfunction "1_1") (pintype "passive"))
    )
    (net (code "52") (name "Net-(LED19-Pad1)") (class "Default")
      (node (ref "LED19") (pin "1") (pinfunction "1_1") (pintype "passive"))
      (node (ref "R109") (pin "1") (pinfunction "1_1") (pintype "passive"))
    )
    (net (code "53") (name "Net-(LED20-Pad1)") (class "Default")
      (node (ref "LED20") (pin "1") (pinfunction "1_1") (pintype "passive"))
      (node (ref "R110") (pin "1") (pinfunction "1_1") (pintype "passive"))
    )
    (net (code "54") (name "Net-(LED21-Pad1)") (class "Default")
      (node (ref "LED21") (pin "1") (pinfunction "1_1") (pintype "passive"))
      (node (ref "R111") (pin "1") (pinfunction "1_1") (pintype "passive"))
    )
    (net (code "55") (name "Net-(Q1-G)") (class "Default")
      (node (ref "Q1") (pin "1") (pinfunction "G_1") (pintype "passive"))
      (node (ref "R67") (pin "1") (pinfunction "1_1") (pintype "passive"))
      (node (ref "R71") (pin "1") (pinfunction "1_1") (pintype "passive"))
    )
    (net (code "56") (name "Net-(Q2-G)") (class "Default")
      (node (ref "Q2") (pin "1") (pinfunction "G_1") (pintype "passive"))
      (node (ref "R68") (pin "1") (pinfunction "1_1") (pintype "passive"))
      (node (ref "R72") (pin "1") (pinfunction "1_1") (pintype "passive"))
    )
    (net (code "57") (name "Net-(Q3-G)") (class "Default")
      (node (ref "Q3") (pin "1") (pinfunction "G_1") (pintype "passive"))
      (node (ref "R69") (pin "1") (pinfunction "1_1") (pintype "passive"))
      (node (ref "R73") (pin "1") (pinfunction "1_1") (pintype "passive"))
    )
    (net (code "58") (name "Net-(Q4-G)") (class "Default")
      (node (ref "Q4") (pin "1") (pinfunction "G_1") (pintype "passive"))
      (node (ref "R70") (pin "1") (pinfunction "1_1") (pintype "passive"))
      (node (ref "R74") (pin "1") (pinfunction "1_1") (pintype "passive"))
    )
    (net (code "59") (name "Net-(Q5-G)") (class "Default")
      (node (ref "Q5") (pin "1") (pinfunction "G_1") (pintype "passive"))
      (node (ref "R75") (pin "1") (pinfunction "1_1") (pintype "passive"))
      (node (ref "R79") (pin "1") (pinfunction "1_1") (pintype "passive"))
    )
    (net (code "60") (name "Net-(Q6-G)") (class "Default")
      (node (ref "Q6") (pin "1") (pinfunction "G_1") (pintype "passive"))
      (node (ref "R76") (pin "1") (pinfunction "1_1") (pintype "passive"))
      (node (ref "R80") (pin "1") (pinfunction "1_1") (pintype "passive"))
    )
    (net (code "61") (name "Net-(Q7-G)") (class "Default")
      (node (ref "Q7") (pin "1") (pinfunction "G_1") (pintype "passive"))
      (node (ref "R77") (pin "1") (pinfunction "1_1") (pintype "passive"))
      (node (ref "R81") (pin "1") (pinfunction "1_1") (pintype "passive"))
    )
    (net (code "62") (name "Net-(Q8-G)") (class "Default")
      (node (ref "Q8") (pin "1") (pinfunction "G_1") (pintype "passive"))
      (node (ref "R78") (pin "1") (pinfunction "1_1") (pintype "passive"))
      (node (ref "R82") (pin "1") (pinfunction "1_1") (pintype "passive"))
    )
    (net (code "63") (name "Net-(Q9-G)") (class "Default")
      (node (ref "Q9") (pin "1") (pinfunction "G_1") (pintype "passive"))
      (node (ref "R83") (pin "1") (pinfunction "1_1") (pintype "passive"))
      (node (ref "R87") (pin "1") (pinfunction "1_1") (pintype "passive"))
    )
    (net (code "64") (name "Net-(Q10-G)") (class "Default")
      (node (ref "Q10") (pin "1") (pinfunction "G_1") (pintype "passive"))
      (node (ref "R84") (pin "1") (pinfunction "1_1") (pintype "passive"))
      (node (ref "R88") (pin "1") (pinfunction "1_1") (pintype "passive"))
    )
    (net (code "65") (name "Net-(Q11-G)") (class "Default")
      (node (ref "Q11") (pin "1") (pinfunction "G_1") (pintype "passive"))
      (node (ref "R85") (pin "1") (pinfunction "1_1") (pintype "passive"))
      (node (ref "R89") (pin "1") (pinfunction "1_1") (pintype "passive"))
    )
    (net (code "66") (name "Net-(Q12-G)") (class "Default")
      (node (ref "Q12") (pin "1") (pinfunction "G_1") (pintype "passive"))
      (node (ref "R86") (pin "1") (pinfunction "1_1") (pintype "passive"))
      (node (ref "R90") (pin "1") (pinfunction "1_1") (pintype "passive"))
    )
    (net (code "67") (name "Net-(Q13-G)") (class "Default")
      (node (ref "Q13") (pin "1") (pinfunction "G_1") (pintype "passive"))
      (node (ref "R91") (pin "1") (pinfunction "1_1") (pintype "passive"))
      (node (ref "R95") (pin "1") (pinfunction "1_1") (pintype "passive"))
    )
    (net (code "68") (name "Net-(Q14-G)") (class "Default")
      (node (ref "Q14") (pin "1") (pinfunction "G_1") (pintype "passive"))
      (node (ref "R92") (pin "1") (pinfunction "1_1") (pintype "passive"))
      (node (ref "R96") (pin "1") (pinfunction "1_1") (pintype "passive"))
    )
    (net (code "69") (name "Net-(Q15-G)") (class "Default")
      (node (ref "Q15") (pin "1") (pinfunction "G_1") (pintype "passive"))
      (node (ref "R93") (pin "1") (pinfunction "1_1") (pintype "passive"))
      (node (ref "R97") (pin "1") (pinfunction "1_1") (pintype "passive"))
    )
    (net (code "70") (name "Net-(Q16-G)") (class "Default")
      (node (ref "Q16") (pin "1") (pinfunction "G_1") (pintype "passive"))
      (node (ref "R94") (pin "1") (pinfunction "1_1") (pintype "passive"))
      (node (ref "R98") (pin "1") (pinfunction "1_1") (pintype "passive"))
    )
  )
)
